# pb-switch-pcb.net
KiCad netlist of a schematic drawn in EAGLE
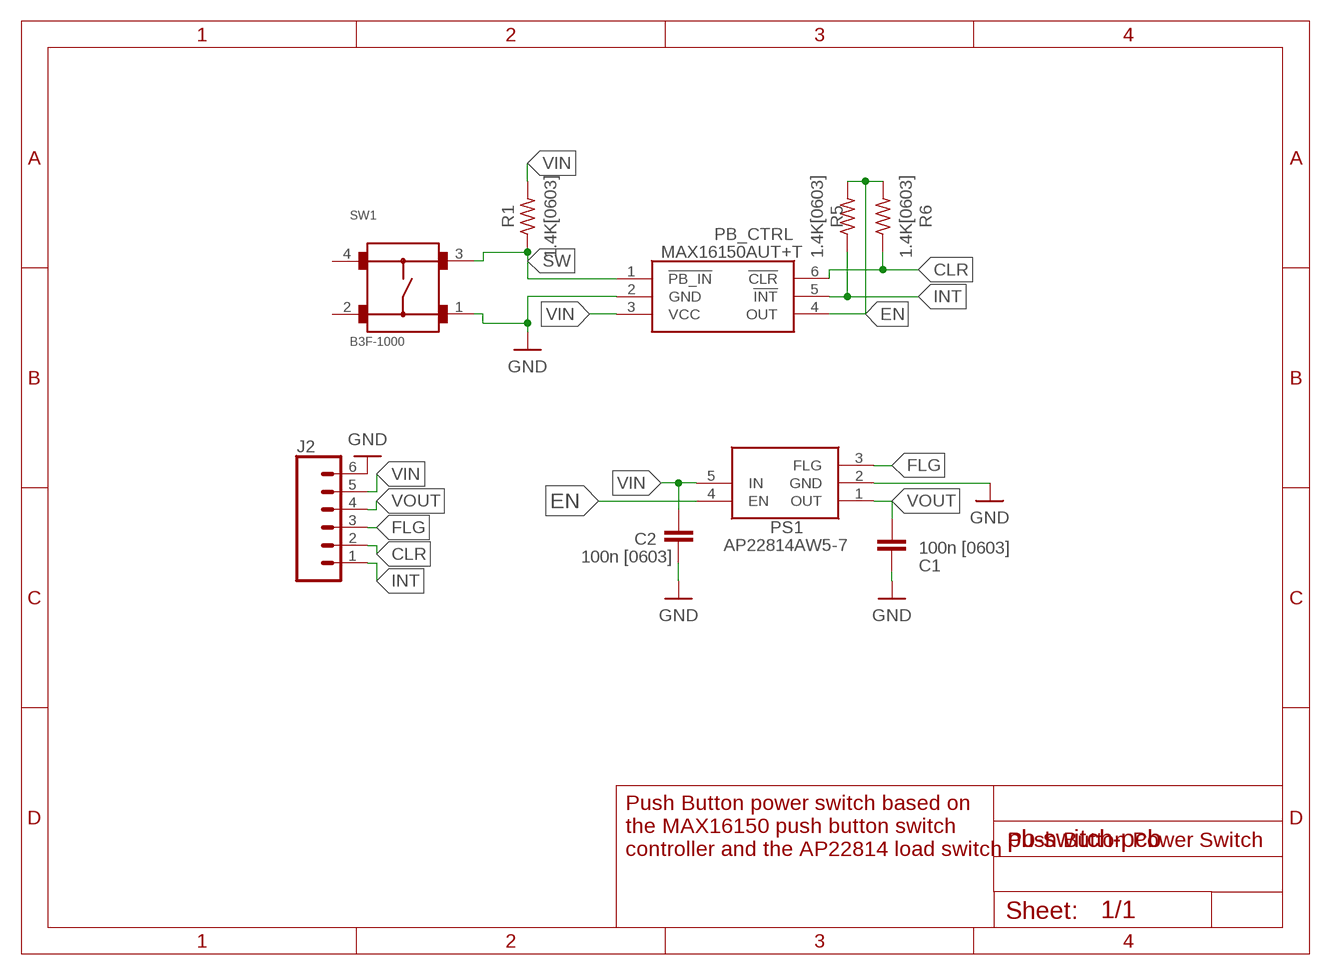
[diagram p0: schematic, sheet 1]

(export (version "E")
  (design (tool "Eeschema 10.0.6"))
  (components
    (comp (ref "C1")
      (value "100n [0603]")
      (footprint "eagle-import:CAPC1608X85")
      (libsource (lib "eagle-import") (part "CCHIP-0603(1608-METRIC)_"))
    )
    (comp (ref "C2")
      (value "100n [0603]")
      (footprint "eagle-import:CAPC1608X85")
      (libsource (lib "eagle-import") (part "CCHIP-0603(1608-METRIC)_"))
    )
    (comp (ref "J2")
      (value "CONN_06SILK_FEMALE_PTH")
      (footprint "eagle-import:1X06")
      (libsource (lib "eagle-import") (part "CONN_06SILK_FEMALE_PTH"))
    )
    (comp (ref "PB_CTRL")
      (value "MAX16150AUT+T")
      (footprint "eagle-import:SOT95P280X145-6N")
      (fields (field (name "MOUSER_PART_NUMBER") "700-MAX16150AUT+T"))
      (libsource (lib "eagle-import") (part "MAX16150AUT+T"))
    )
    (comp (ref "PS1")
      (value "AP22814AW5-7")
      (footprint "eagle-import:SOT95P285X130-5N")
      (fields (field (name "MOUSER_PART_NUMBER") "621-AP22814AW5-7"))
      (libsource (lib "eagle-import") (part "AP22814AW5-7"))
    )
    (comp (ref "R1")
      (value "1.4K[0603]")
      (footprint "eagle-import:RESC1608X60")
      (libsource (lib "eagle-import") (part "R-USCHIP-0603(1608-METRIC)_"))
    )
    (comp (ref "R5")
      (value "1.4K[0603]")
      (footprint "eagle-import:RESC1608X60")
      (libsource (lib "eagle-import") (part "R-USCHIP-0603(1608-METRIC)_"))
    )
    (comp (ref "R6")
      (value "1.4K[0603]")
      (footprint "eagle-import:RESC1608X60")
      (libsource (lib "eagle-import") (part "R-USCHIP-0603(1608-METRIC)_"))
    )
    (comp (ref "SW1")
      (value "B3F-1000")
      (footprint "eagle-import:B3F-1000")
      (fields
        (field (name "DIGI_KEY_PART_NUMBER") "SW400-ND")
        (field (name "MANUFACTURER") "Omron Electronics Inc-EMC Div")
        (field (name "CREATED_BY") "PCBLayout.com")
      )
      (libsource (lib "eagle-import") (part "B3F-1000"))
    )
  )
  (nets
    (net (code "1") (name "CLR") (class "Default")
      (node (ref "J2") (pin "2") (pinfunction "2_2") (pintype "passive"))
      (node (ref "PB_CTRL") (pin "6") (pinfunction "~{CLR}_6") (pintype "bidirectional"))
      (node (ref "R6") (pin "1") (pinfunction "1_1") (pintype "passive"))
    )
    (net (code "2") (name "EN") (class "Default")
      (node (ref "PB_CTRL") (pin "4") (pinfunction "OUT_4") (pintype "bidirectional"))
      (node (ref "PS1") (pin "4") (pinfunction "EN_4") (pintype "input"))
      (node (ref "R5") (pin "2") (pinfunction "2_2") (pintype "passive"))
      (node (ref "R6") (pin "2") (pinfunction "2_2") (pintype "passive"))
    )
    (net (code "3") (name "FLG") (class "Default")
      (node (ref "J2") (pin "3") (pinfunction "3_3") (pintype "passive"))
      (node (ref "PS1") (pin "3") (pinfunction "FLG_3") (pintype "bidirectional"))
    )
    (net (code "4") (name "GND") (class "Default")
      (node (ref "C1") (pin "2") (pinfunction "2_2") (pintype "passive"))
      (node (ref "C2") (pin "2") (pinfunction "2_2") (pintype "passive"))
      (node (ref "J2") (pin "6") (pinfunction "6_6") (pintype "passive"))
      (node (ref "PB_CTRL") (pin "2") (pinfunction "GND_2") (pintype "bidirectional"))
      (node (ref "PS1") (pin "2") (pinfunction "GND_2") (pintype "power_in"))
      (node (ref "SW1") (pin "1") (pinfunction "1_1") (pintype "passive"))
    )
    (net (code "5") (name "INT") (class "Default")
      (node (ref "J2") (pin "1") (pinfunction "1_1") (pintype "passive"))
      (node (ref "PB_CTRL") (pin "5") (pinfunction "~{INT}_5") (pintype "bidirectional"))
      (node (ref "R5") (pin "1") (pinfunction "1_1") (pintype "passive"))
    )
    (net (code "6") (name "SW") (class "Default")
      (node (ref "PB_CTRL") (pin "1") (pinfunction "~{PB_IN}_1") (pintype "bidirectional"))
      (node (ref "R1") (pin "1") (pinfunction "1_1") (pintype "passive"))
      (node (ref "SW1") (pin "3") (pinfunction "3_3") (pintype "passive"))
    )
    (net (code "7") (name "VIN") (class "Default")
      (node (ref "C2") (pin "1") (pinfunction "1_1") (pintype "passive"))
      (node (ref "J2") (pin "5") (pinfunction "5_5") (pintype "passive"))
      (node (ref "PB_CTRL") (pin "3") (pinfunction "VCC_3") (pintype "bidirectional"))
      (node (ref "PS1") (pin "5") (pinfunction "IN_5") (pintype "power_in"))
      (node (ref "R1") (pin "2") (pinfunction "2_2") (pintype "passive"))
    )
    (net (code "8") (name "VOUT") (class "Default")
      (node (ref "C1") (pin "1") (pinfunction "1_1") (pintype "passive"))
      (node (ref "J2") (pin "4") (pinfunction "4_4") (pintype "passive"))
      (node (ref "PS1") (pin "1") (pinfunction "OUT_1") (pintype "power_in"))
    )
    (net (code "9") (name "unconnected-(SW1-Pad2)") (class "Default")
      (node (ref "SW1") (pin "2") (pinfunction "2_2") (pintype "passive"))
    )
    (net (code "10") (name "unconnected-(SW1-Pad4)") (class "Default")
      (node (ref "SW1") (pin "4") (pinfunction "4_4") (pintype "passive"))
    )
  )
)
